# power_supplies.net
KiCad netlist of a schematic drawn in Altium Designer
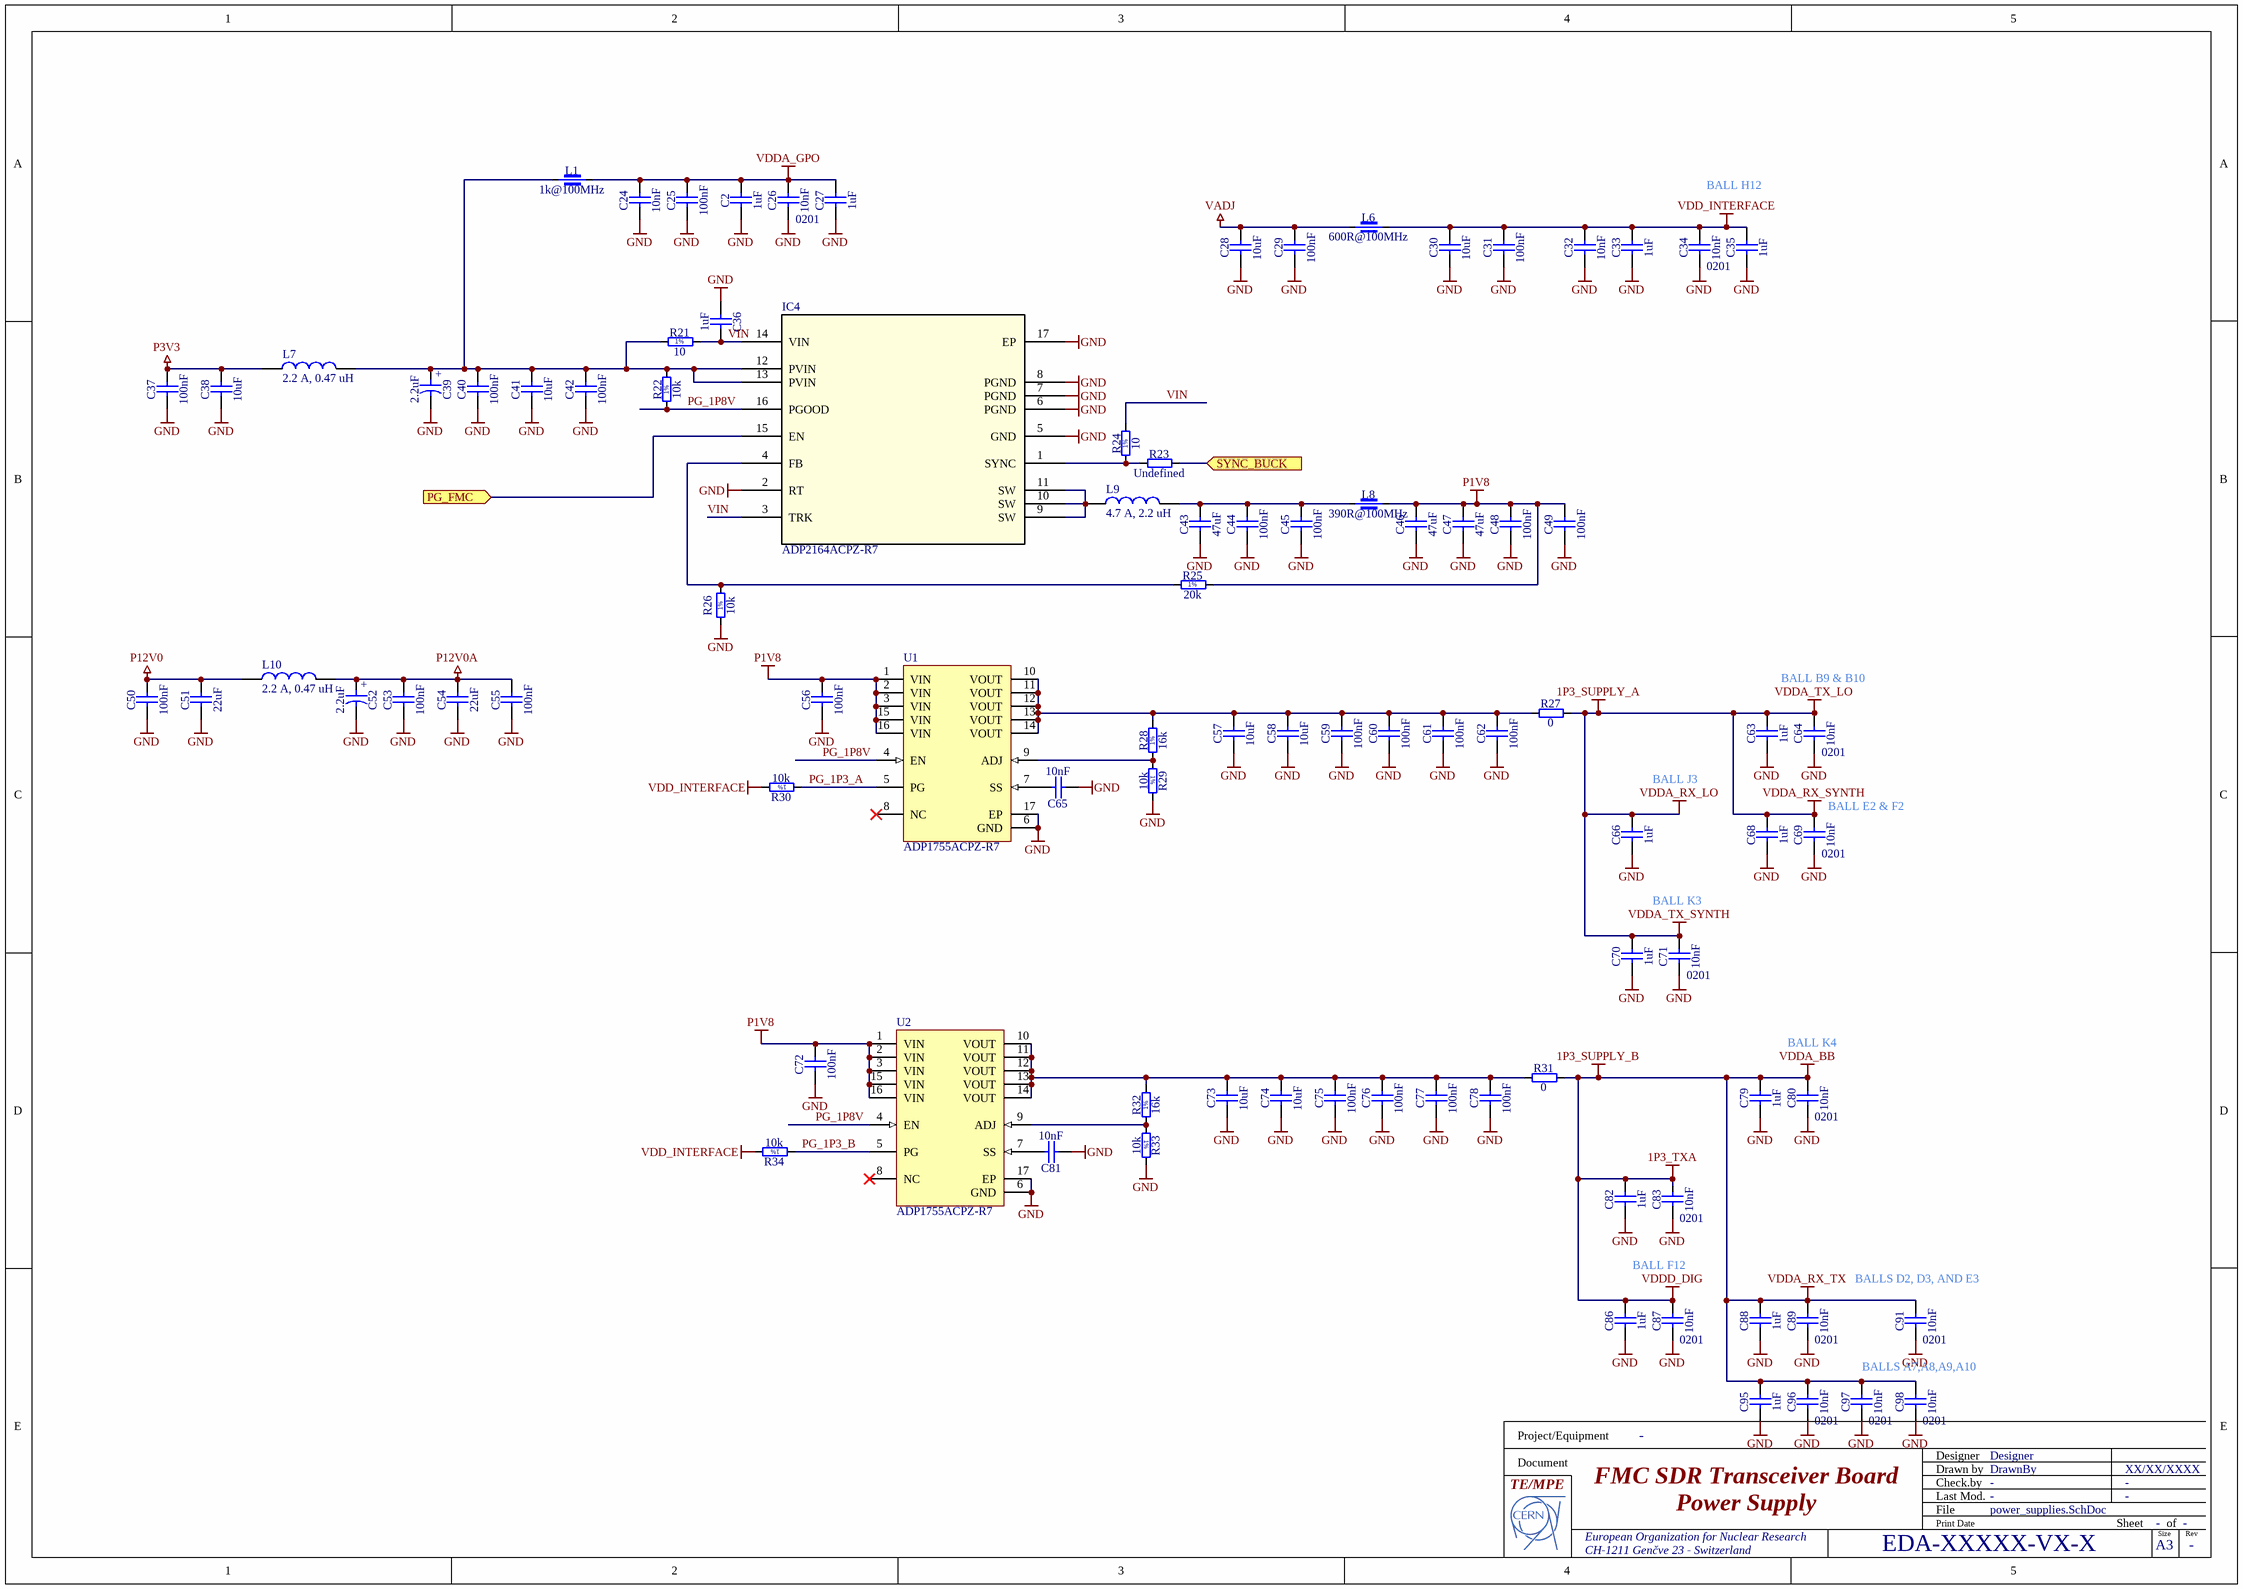
[diagram p0: power_supplies.SchDoc]

(export (version "E")
  (design (tool "Eeschema 10.0.6"))
  (components
    (comp (ref "C2")
      (value "1uF")
      (footprint "CAPC1005X55N")
      (description "Non-polarised capacitor")
      (fields
        (field (name "PART NUMBER") "CC0402_1UF_16V_10%_X5R")
        (field (name "VOLTAGE") "16V")
        (field (name "AUTHOR") "CERN DEM JLC")
      )
      (libsource (lib "Capacitors") (part "Capacitor - non polarized"))
    )
    (comp (ref "C24")
      (value "10nF")
      (footprint "CAPC1005X55N")
      (description "Non-polarised capacitor")
      (fields
        (field (name "PART NUMBER") "CC0402_10NF_16V_10%_X7R")
        (field (name "VOLTAGE") "16V")
        (field (name "AUTHOR") "CERN DEM JLC")
      )
      (libsource (lib "Capacitors") (part "Capacitor - non polarized"))
    )
    (comp (ref "C25")
      (value "100nF")
      (footprint "CAPC1005X55N")
      (description "Non-polarised capacitor")
      (fields
        (field (name "PART NUMBER") "CC0402_100NF_16V_10%_X7R")
        (field (name "VOLTAGE") "16V")
        (field (name "AUTHOR") "CERN DEM JLC")
      )
      (libsource (lib "Capacitors") (part "Capacitor - non polarized"))
    )
    (comp (ref "C26")
      (value "10nF")
      (footprint "CAPC0603X33N")
      (description "Non-polarised capacitor")
      (fields
        (field (name "PART NUMBER") "CC0201_10NF_10V_10%_X5R")
        (field (name "VOLTAGE") "10V")
        (field (name "CASE") "0201")
        (field (name "AUTHOR") "CERN DEM JLC")
      )
      (libsource (lib "Capacitors") (part "Capacitor - non polarized"))
    )
    (comp (ref "C27")
      (value "1uF")
      (footprint "CAPC1005X55N")
      (description "Non-polarised capacitor")
      (fields
        (field (name "PART NUMBER") "CC0402_1UF_16V_10%_X5R")
        (field (name "VOLTAGE") "16V")
        (field (name "AUTHOR") "CERN DEM JLC")
      )
      (libsource (lib "Capacitors") (part "Capacitor - non polarized"))
    )
    (comp (ref "C28")
      (value "10uF")
      (footprint "CAPC1608X87N")
      (description "Non-polarised capacitor")
      (fields
        (field (name "PART NUMBER") "CC0603_10UF_6.3V_20%_X5R")
        (field (name "VOLTAGE") "6.3V")
        (field (name "AUTHOR") "CERN DEM JLC")
      )
      (libsource (lib "Capacitors") (part "Capacitor - non polarized"))
    )
    (comp (ref "C29")
      (value "100nF")
      (footprint "CAPC1005X55N")
      (description "Non-polarised capacitor")
      (fields
        (field (name "PART NUMBER") "CC0402_100NF_16V_10%_X7R")
        (field (name "VOLTAGE") "16V")
        (field (name "AUTHOR") "CERN DEM JLC")
      )
      (libsource (lib "Capacitors") (part "Capacitor - non polarized"))
    )
    (comp (ref "C30")
      (value "10uF")
      (footprint "CAPC1608X87N")
      (description "Non-polarised capacitor")
      (fields
        (field (name "PART NUMBER") "CC0603_10UF_6.3V_20%_X5R")
        (field (name "VOLTAGE") "6.3V")
        (field (name "AUTHOR") "CERN DEM JLC")
      )
      (libsource (lib "Capacitors") (part "Capacitor - non polarized"))
    )
    (comp (ref "C31")
      (value "100nF")
      (footprint "CAPC1005X55N")
      (description "Non-polarised capacitor")
      (fields
        (field (name "PART NUMBER") "CC0402_100NF_16V_10%_X7R")
        (field (name "VOLTAGE") "16V")
        (field (name "AUTHOR") "CERN DEM JLC")
      )
      (libsource (lib "Capacitors") (part "Capacitor - non polarized"))
    )
    (comp (ref "C32")
      (value "10nF")
      (footprint "CAPC1005X55N")
      (description "Non-polarised capacitor")
      (fields
        (field (name "PART NUMBER") "CC0402_10NF_16V_10%_X7R")
        (field (name "VOLTAGE") "16V")
        (field (name "AUTHOR") "CERN DEM JLC")
      )
      (libsource (lib "Capacitors") (part "Capacitor - non polarized"))
    )
    (comp (ref "C33")
      (value "1uF")
      (footprint "CAPC1005X55N")
      (description "Non-polarised capacitor")
      (fields
        (field (name "PART NUMBER") "CC0402_1UF_16V_10%_X5R")
        (field (name "VOLTAGE") "16V")
        (field (name "AUTHOR") "CERN DEM JLC")
      )
      (libsource (lib "Capacitors") (part "Capacitor - non polarized"))
    )
    (comp (ref "C34")
      (value "10nF")
      (footprint "CAPC0603X33N")
      (description "Non-polarised capacitor")
      (fields
        (field (name "PART NUMBER") "CC0201_10NF_10V_10%_X5R")
        (field (name "VOLTAGE") "10V")
        (field (name "CASE") "0201")
        (field (name "AUTHOR") "CERN DEM JLC")
      )
      (libsource (lib "Capacitors") (part "Capacitor - non polarized"))
    )
    (comp (ref "C35")
      (value "1uF")
      (footprint "CAPC1005X55N")
      (description "Non-polarised capacitor")
      (fields
        (field (name "PART NUMBER") "CC0402_1UF_16V_10%_X5R")
        (field (name "VOLTAGE") "16V")
        (field (name "AUTHOR") "CERN DEM JLC")
      )
      (libsource (lib "Capacitors") (part "Capacitor - non polarized"))
    )
    (comp (ref "C36")
      (value "1uF")
      (footprint "CAPC1005X55N")
      (description "Non-polarised capacitor")
      (fields
        (field (name "PART NUMBER") "CC0402_1UF_16V_10%_X5R")
        (field (name "VOLTAGE") "16V")
        (field (name "AUTHOR") "CERN DEM JLC")
      )
      (libsource (lib "Capacitors") (part "Capacitor - non polarized"))
    )
    (comp (ref "C37")
      (value "100nF")
      (footprint "CAPC1005X55N")
      (description "Non-polarised capacitor")
      (fields
        (field (name "PART NUMBER") "CC0402_100NF_16V_10%_X7R")
        (field (name "VOLTAGE") "16V")
        (field (name "AUTHOR") "CERN DEM JLC")
      )
      (libsource (lib "Capacitors") (part "Capacitor - non polarized"))
    )
    (comp (ref "C38")
      (value "10uF")
      (footprint "CAPC1608X87N")
      (description "Non-polarised capacitor")
      (fields
        (field (name "PART NUMBER") "CC0603_10UF_6.3V_20%_X5R")
        (field (name "VOLTAGE") "6.3V")
        (field (name "AUTHOR") "CERN DEM JLC")
      )
      (libsource (lib "Capacitors") (part "Capacitor - non polarized"))
    )
    (comp (ref "C39")
      (value "2.2uF")
      (footprint "CAPMP3216X180N")
      (description "Polarised capacitor")
      (fields
        (field (name "PART NUMBER") "CTE3216-18_2.2UF_25V_10%")
        (field (name "VOLTAGE") "25V")
        (field (name "AUTHOR") "CERN DEM JLC")
      )
      (libsource (lib "Capacitors") (part "Capacitor - polarized"))
    )
    (comp (ref "C40")
      (value "100nF")
      (footprint "CAPC1005X55N")
      (description "Non-polarised capacitor")
      (fields
        (field (name "PART NUMBER") "CC0402_100NF_16V_10%_X7R")
        (field (name "VOLTAGE") "16V")
        (field (name "AUTHOR") "CERN DEM JLC")
      )
      (libsource (lib "Capacitors") (part "Capacitor - non polarized"))
    )
    (comp (ref "C41")
      (value "10uF")
      (footprint "CAPC1608X87N")
      (description "Non-polarised capacitor")
      (fields
        (field (name "PART NUMBER") "CC0603_10UF_6.3V_20%_X5R")
        (field (name "VOLTAGE") "6.3V")
        (field (name "AUTHOR") "CERN DEM JLC")
      )
      (libsource (lib "Capacitors") (part "Capacitor - non polarized"))
    )
    (comp (ref "C42")
      (value "100nF")
      (footprint "CAPC1005X55N")
      (description "Non-polarised capacitor")
      (fields
        (field (name "PART NUMBER") "CC0402_100NF_16V_10%_X7R")
        (field (name "VOLTAGE") "16V")
        (field (name "AUTHOR") "CERN DEM JLC")
      )
      (libsource (lib "Capacitors") (part "Capacitor - non polarized"))
    )
    (comp (ref "C43")
      (value "47uF")
      (footprint "CAPC3216X180N")
      (description "Non-polarised capacitor")
      (fields
        (field (name "PART NUMBER") "CC1206_47UF_25V_20%_X5R")
        (field (name "VOLTAGE") "25V")
        (field (name "AUTHOR") "CERN DEM JLC")
      )
      (libsource (lib "Capacitors") (part "Capacitor - non polarized"))
    )
    (comp (ref "C44")
      (value "100nF")
      (footprint "CAPC1005X55N")
      (description "Non-polarised capacitor")
      (fields
        (field (name "PART NUMBER") "CC0402_100NF_16V_10%_X7R")
        (field (name "VOLTAGE") "16V")
        (field (name "AUTHOR") "CERN DEM JLC")
      )
      (libsource (lib "Capacitors") (part "Capacitor - non polarized"))
    )
    (comp (ref "C45")
      (value "100nF")
      (footprint "CAPC1005X55N")
      (description "Non-polarised capacitor")
      (fields
        (field (name "PART NUMBER") "CC0402_100NF_16V_10%_X7R")
        (field (name "VOLTAGE") "16V")
        (field (name "AUTHOR") "CERN DEM JLC")
      )
      (libsource (lib "Capacitors") (part "Capacitor - non polarized"))
    )
    (comp (ref "C46")
      (value "47uF")
      (footprint "CAPC3216X180N")
      (description "Non-polarised capacitor")
      (fields
        (field (name "PART NUMBER") "CC1206_47UF_25V_20%_X5R")
        (field (name "VOLTAGE") "25V")
        (field (name "AUTHOR") "CERN DEM JLC")
      )
      (libsource (lib "Capacitors") (part "Capacitor - non polarized"))
    )
    (comp (ref "C47")
      (value "47uF")
      (footprint "CAPC3216X180N")
      (description "Non-polarised capacitor")
      (fields
        (field (name "PART NUMBER") "CC1206_47UF_25V_20%_X5R")
        (field (name "VOLTAGE") "25V")
        (field (name "AUTHOR") "CERN DEM JLC")
      )
      (libsource (lib "Capacitors") (part "Capacitor - non polarized"))
    )
    (comp (ref "C48")
      (value "100nF")
      (footprint "CAPC1005X55N")
      (description "Non-polarised capacitor")
      (fields
        (field (name "PART NUMBER") "CC0402_100NF_16V_10%_X7R")
        (field (name "VOLTAGE") "16V")
        (field (name "AUTHOR") "CERN DEM JLC")
      )
      (libsource (lib "Capacitors") (part "Capacitor - non polarized"))
    )
    (comp (ref "C49")
      (value "100nF")
      (footprint "CAPC1005X55N")
      (description "Non-polarised capacitor")
      (fields
        (field (name "PART NUMBER") "CC0402_100NF_16V_10%_X7R")
        (field (name "VOLTAGE") "16V")
        (field (name "AUTHOR") "CERN DEM JLC")
      )
      (libsource (lib "Capacitors") (part "Capacitor - non polarized"))
    )
    (comp (ref "C50")
      (value "100nF")
      (footprint "CAPC1005X55N")
      (description "Non-polarised capacitor")
      (fields
        (field (name "PART NUMBER") "CC0402_100NF_16V_10%_X7R")
        (field (name "VOLTAGE") "16V")
        (field (name "AUTHOR") "CERN DEM JLC")
      )
      (libsource (lib "Capacitors") (part "Capacitor - non polarized"))
    )
    (comp (ref "C51")
      (value "22uF")
      (footprint "CAPC3216X180N")
      (description "Non-polarised capacitor")
      (fields
        (field (name "PART NUMBER") "CC1206_22UF_35V_20%_JB_TDK_C3216JB1V226M160AC")
        (field (name "VOLTAGE") "35V")
        (field (name "AUTHOR") "CERN DEM JLC")
      )
      (libsource (lib "Capacitors") (part "Capacitor - non polarized"))
    )
    (comp (ref "C52")
      (value "2.2uF")
      (footprint "CAPMP3216X180N")
      (description "Polarised capacitor")
      (fields
        (field (name "PART NUMBER") "CTE3216-18_2.2UF_25V_10%")
        (field (name "VOLTAGE") "25V")
        (field (name "AUTHOR") "CERN DEM JLC")
      )
      (libsource (lib "Capacitors") (part "Capacitor - polarized"))
    )
    (comp (ref "C53")
      (value "100nF")
      (footprint "CAPC1005X55N")
      (description "Non-polarised capacitor")
      (fields
        (field (name "PART NUMBER") "CC0402_100NF_16V_10%_X7R")
        (field (name "VOLTAGE") "16V")
        (field (name "AUTHOR") "CERN DEM JLC")
      )
      (libsource (lib "Capacitors") (part "Capacitor - non polarized"))
    )
    (comp (ref "C54")
      (value "22uF")
      (footprint "CAPC3216X180N")
      (description "Non-polarised capacitor")
      (fields
        (field (name "PART NUMBER") "CC1206_22UF_35V_20%_JB_TDK_C3216JB1V226M160AC")
        (field (name "VOLTAGE") "35V")
        (field (name "AUTHOR") "CERN DEM JLC")
      )
      (libsource (lib "Capacitors") (part "Capacitor - non polarized"))
    )
    (comp (ref "C55")
      (value "100nF")
      (footprint "CAPC1005X55N")
      (description "Non-polarised capacitor")
      (fields
        (field (name "PART NUMBER") "CC0402_100NF_16V_10%_X7R")
        (field (name "VOLTAGE") "16V")
        (field (name "AUTHOR") "CERN DEM JLC")
      )
      (libsource (lib "Capacitors") (part "Capacitor - non polarized"))
    )
    (comp (ref "C56")
      (value "100nF")
      (footprint "CAPC1005X55N")
      (description "Non-polarised capacitor")
      (fields
        (field (name "PART NUMBER") "CC0402_100NF_16V_10%_X7R")
        (field (name "VOLTAGE") "16V")
        (field (name "AUTHOR") "CERN DEM JLC")
      )
      (libsource (lib "Capacitors") (part "Capacitor - non polarized"))
    )
    (comp (ref "C57")
      (value "10uF")
      (footprint "CAPC1608X87N")
      (description "Non-polarised capacitor")
      (fields
        (field (name "PART NUMBER") "CC0603_10UF_6.3V_20%_X5R")
        (field (name "VOLTAGE") "6.3V")
        (field (name "AUTHOR") "CERN DEM JLC")
      )
      (libsource (lib "Capacitors") (part "Capacitor - non polarized"))
    )
    (comp (ref "C58")
      (value "10uF")
      (footprint "CAPC1608X87N")
      (description "Non-polarised capacitor")
      (fields
        (field (name "PART NUMBER") "CC0603_10UF_6.3V_20%_X5R")
        (field (name "VOLTAGE") "6.3V")
        (field (name "AUTHOR") "CERN DEM JLC")
      )
      (libsource (lib "Capacitors") (part "Capacitor - non polarized"))
    )
    (comp (ref "C59")
      (value "100nF")
      (footprint "CAPC1005X55N")
      (description "Non-polarised capacitor")
      (fields
        (field (name "PART NUMBER") "CC0402_100NF_16V_10%_X7R")
        (field (name "VOLTAGE") "16V")
        (field (name "AUTHOR") "CERN DEM JLC")
      )
      (libsource (lib "Capacitors") (part "Capacitor - non polarized"))
    )
    (comp (ref "C60")
      (value "100nF")
      (footprint "CAPC1005X55N")
      (description "Non-polarised capacitor")
      (fields
        (field (name "PART NUMBER") "CC0402_100NF_16V_10%_X7R")
        (field (name "VOLTAGE") "16V")
        (field (name "AUTHOR") "CERN DEM JLC")
      )
      (libsource (lib "Capacitors") (part "Capacitor - non polarized"))
    )
    (comp (ref "C61")
      (value "100nF")
      (footprint "CAPC1005X55N")
      (description "Non-polarised capacitor")
      (fields
        (field (name "PART NUMBER") "CC0402_100NF_16V_10%_X7R")
        (field (name "VOLTAGE") "16V")
        (field (name "AUTHOR") "CERN DEM JLC")
      )
      (libsource (lib "Capacitors") (part "Capacitor - non polarized"))
    )
    (comp (ref "C62")
      (value "100nF")
      (footprint "CAPC1005X55N")
      (description "Non-polarised capacitor")
      (fields
        (field (name "PART NUMBER") "CC0402_100NF_16V_10%_X7R")
        (field (name "VOLTAGE") "16V")
        (field (name "AUTHOR") "CERN DEM JLC")
      )
      (libsource (lib "Capacitors") (part "Capacitor - non polarized"))
    )
    (comp (ref "C63")
      (value "1uF")
      (footprint "CAPC1005X55N")
      (description "Non-polarised capacitor")
      (fields
        (field (name "PART NUMBER") "CC0402_1UF_16V_10%_X5R")
        (field (name "VOLTAGE") "16V")
        (field (name "AUTHOR") "CERN DEM JLC")
      )
      (libsource (lib "Capacitors") (part "Capacitor - non polarized"))
    )
    (comp (ref "C64")
      (value "10nF")
      (footprint "CAPC0603X33N")
      (description "Non-polarised capacitor")
      (fields
        (field (name "PART NUMBER") "CC0201_10NF_10V_10%_X5R")
        (field (name "VOLTAGE") "10V")
        (field (name "CASE") "0201")
        (field (name "AUTHOR") "CERN DEM JLC")
      )
      (libsource (lib "Capacitors") (part "Capacitor - non polarized"))
    )
    (comp (ref "C65")
      (value "10nF")
      (footprint "CAPC1005X55N")
      (description "Non-polarised capacitor")
      (fields
        (field (name "PART NUMBER") "CC0402_10NF_16V_10%_X7R")
        (field (name "VOLTAGE") "16V")
        (field (name "AUTHOR") "CERN DEM JLC")
      )
      (libsource (lib "Capacitors") (part "Capacitor - non polarized"))
    )
    (comp (ref "C66")
      (value "1uF")
      (footprint "CAPC1005X55N")
      (description "Non-polarised capacitor")
      (fields
        (field (name "PART NUMBER") "CC0402_1UF_16V_10%_X5R")
        (field (name "VOLTAGE") "16V")
        (field (name "AUTHOR") "CERN DEM JLC")
      )
      (libsource (lib "Capacitors") (part "Capacitor - non polarized"))
    )
    (comp (ref "C68")
      (value "1uF")
      (footprint "CAPC1005X55N")
      (description "Non-polarised capacitor")
      (fields
        (field (name "PART NUMBER") "CC0402_1UF_16V_10%_X5R")
        (field (name "VOLTAGE") "16V")
        (field (name "AUTHOR") "CERN DEM JLC")
      )
      (libsource (lib "Capacitors") (part "Capacitor - non polarized"))
    )
    (comp (ref "C69")
      (value "10nF")
      (footprint "CAPC0603X33N")
      (description "Non-polarised capacitor")
      (fields
        (field (name "PART NUMBER") "CC0201_10NF_10V_10%_X5R")
        (field (name "VOLTAGE") "10V")
        (field (name "CASE") "0201")
        (field (name "AUTHOR") "CERN DEM JLC")
      )
      (libsource (lib "Capacitors") (part "Capacitor - non polarized"))
    )
    (comp (ref "C70")
      (value "1uF")
      (footprint "CAPC1005X55N")
      (description "Non-polarised capacitor")
      (fields
        (field (name "PART NUMBER") "CC0402_1UF_16V_10%_X5R")
        (field (name "VOLTAGE") "16V")
        (field (name "AUTHOR") "CERN DEM JLC")
      )
      (libsource (lib "Capacitors") (part "Capacitor - non polarized"))
    )
    (comp (ref "C71")
      (value "10nF")
      (footprint "CAPC0603X33N")
      (description "Non-polarised capacitor")
      (fields
        (field (name "PART NUMBER") "CC0201_10NF_10V_10%_X5R")
        (field (name "VOLTAGE") "10V")
        (field (name "CASE") "0201")
        (field (name "AUTHOR") "CERN DEM JLC")
      )
      (libsource (lib "Capacitors") (part "Capacitor - non polarized"))
    )
    (comp (ref "C72")
      (value "100nF")
      (footprint "CAPC1005X55N")
      (description "Non-polarised capacitor")
      (fields
        (field (name "PART NUMBER") "CC0402_100NF_16V_10%_X7R")
        (field (name "VOLTAGE") "16V")
        (field (name "AUTHOR") "CERN DEM JLC")
      )
      (libsource (lib "Capacitors") (part "Capacitor - non polarized"))
    )
    (comp (ref "C73")
      (value "10uF")
      (footprint "CAPC1608X87N")
      (description "Non-polarised capacitor")
      (fields
        (field (name "PART NUMBER") "CC0603_10UF_6.3V_20%_X5R")
        (field (name "VOLTAGE") "6.3V")
        (field (name "AUTHOR") "CERN DEM JLC")
      )
      (libsource (lib "Capacitors") (part "Capacitor - non polarized"))
    )
    (comp (ref "C74")
      (value "10uF")
      (footprint "CAPC1608X87N")
      (description "Non-polarised capacitor")
      (fields
        (field (name "PART NUMBER") "CC0603_10UF_6.3V_20%_X5R")
        (field (name "VOLTAGE") "6.3V")
        (field (name "AUTHOR") "CERN DEM JLC")
      )
      (libsource (lib "Capacitors") (part "Capacitor - non polarized"))
    )
    (comp (ref "C75")
      (value "100nF")
      (footprint "CAPC1005X55N")
      (description "Non-polarised capacitor")
      (fields
        (field (name "PART NUMBER") "CC0402_100NF_16V_10%_X7R")
        (field (name "VOLTAGE") "16V")
        (field (name "AUTHOR") "CERN DEM JLC")
      )
      (libsource (lib "Capacitors") (part "Capacitor - non polarized"))
    )
    (comp (ref "C76")
      (value "100nF")
      (footprint "CAPC1005X55N")
      (description "Non-polarised capacitor")
      (fields
        (field (name "PART NUMBER") "CC0402_100NF_16V_10%_X7R")
        (field (name "VOLTAGE") "16V")
        (field (name "AUTHOR") "CERN DEM JLC")
      )
      (libsource (lib "Capacitors") (part "Capacitor - non polarized"))
    )
    (comp (ref "C77")
      (value "100nF")
      (footprint "CAPC1005X55N")
      (description "Non-polarised capacitor")
      (fields
        (field (name "PART NUMBER") "CC0402_100NF_16V_10%_X7R")
        (field (name "VOLTAGE") "16V")
        (field (name "AUTHOR") "CERN DEM JLC")
      )
      (libsource (lib "Capacitors") (part "Capacitor - non polarized"))
    )
    (comp (ref "C78")
      (value "100nF")
      (footprint "CAPC1005X55N")
      (description "Non-polarised capacitor")
      (fields
        (field (name "PART NUMBER") "CC0402_100NF_16V_10%_X7R")
        (field (name "VOLTAGE") "16V")
        (field (name "AUTHOR") "CERN DEM JLC")
      )
      (libsource (lib "Capacitors") (part "Capacitor - non polarized"))
    )
    (comp (ref "C79")
      (value "1uF")
      (footprint "CAPC1005X55N")
      (description "Non-polarised capacitor")
      (fields
        (field (name "PART NUMBER") "CC0402_1UF_16V_10%_X5R")
        (field (name "VOLTAGE") "16V")
        (field (name "AUTHOR") "CERN DEM JLC")
      )
      (libsource (lib "Capacitors") (part "Capacitor - non polarized"))
    )
    (comp (ref "C80")
      (value "10nF")
      (footprint "CAPC0603X33N")
      (description "Non-polarised capacitor")
      (fields
        (field (name "PART NUMBER") "CC0201_10NF_10V_10%_X5R")
        (field (name "VOLTAGE") "10V")
        (field (name "CASE") "0201")
        (field (name "AUTHOR") "CERN DEM JLC")
      )
      (libsource (lib "Capacitors") (part "Capacitor - non polarized"))
    )
    (comp (ref "C81")
      (value "10nF")
      (footprint "CAPC1005X55N")
      (description "Non-polarised capacitor")
      (fields
        (field (name "PART NUMBER") "CC0402_10NF_16V_10%_X7R")
        (field (name "VOLTAGE") "16V")
        (field (name "AUTHOR") "CERN DEM JLC")
      )
      (libsource (lib "Capacitors") (part "Capacitor - non polarized"))
    )
    (comp (ref "C82")
      (value "1uF")
      (footprint "CAPC1005X55N")
      (description "Non-polarised capacitor")
      (fields
        (field (name "PART NUMBER") "CC0402_1UF_16V_10%_X5R")
        (field (name "VOLTAGE") "16V")
        (field (name "AUTHOR") "CERN DEM JLC")
      )
      (libsource (lib "Capacitors") (part "Capacitor - non polarized"))
    )
    (comp (ref "C83")
      (value "10nF")
      (footprint "CAPC0603X33N")
      (description "Non-polarised capacitor")
      (fields
        (field (name "PART NUMBER") "CC0201_10NF_10V_10%_X5R")
        (field (name "VOLTAGE") "10V")
        (field (name "CASE") "0201")
        (field (name "AUTHOR") "CERN DEM JLC")
      )
      (libsource (lib "Capacitors") (part "Capacitor - non polarized"))
    )
    (comp (ref "C86")
      (value "1uF")
      (footprint "CAPC1005X55N")
      (description "Non-polarised capacitor")
      (fields
        (field (name "PART NUMBER") "CC0402_1UF_16V_10%_X5R")
        (field (name "VOLTAGE") "16V")
        (field (name "AUTHOR") "CERN DEM JLC")
      )
      (libsource (lib "Capacitors") (part "Capacitor - non polarized"))
    )
    (comp (ref "C87")
      (value "10nF")
      (footprint "CAPC0603X33N")
      (description "Non-polarised capacitor")
      (fields
        (field (name "PART NUMBER") "CC0201_10NF_10V_10%_X5R")
        (field (name "VOLTAGE") "10V")
        (field (name "CASE") "0201")
        (field (name "AUTHOR") "CERN DEM JLC")
      )
      (libsource (lib "Capacitors") (part "Capacitor - non polarized"))
    )
    (comp (ref "C88")
      (value "1uF")
      (footprint "CAPC1005X55N")
      (description "Non-polarised capacitor")
      (fields
        (field (name "PART NUMBER") "CC0402_1UF_16V_10%_X5R")
        (field (name "VOLTAGE") "16V")
        (field (name "AUTHOR") "CERN DEM JLC")
      )
      (libsource (lib "Capacitors") (part "Capacitor - non polarized"))
    )
    (comp (ref "C89")
      (value "10nF")
      (footprint "CAPC0603X33N")
      (description "Non-polarised capacitor")
      (fields
        (field (name "PART NUMBER") "CC0201_10NF_10V_10%_X5R")
        (field (name "VOLTAGE") "10V")
        (field (name "CASE") "0201")
        (field (name "AUTHOR") "CERN DEM JLC")
      )
      (libsource (lib "Capacitors") (part "Capacitor - non polarized"))
    )
    (comp (ref "C91")
      (value "10nF")
      (footprint "CAPC0603X33N")
      (description "Non-polarised capacitor")
      (fields
        (field (name "PART NUMBER") "CC0201_10NF_10V_10%_X5R")
        (field (name "VOLTAGE") "10V")
        (field (name "CASE") "0201")
        (field (name "AUTHOR") "CERN DEM JLC")
      )
      (libsource (lib "Capacitors") (part "Capacitor - non polarized"))
    )
    (comp (ref "C95")
      (value "1uF")
      (footprint "CAPC1005X55N")
      (description "Non-polarised capacitor")
      (fields
        (field (name "PART NUMBER") "CC0402_1UF_16V_10%_X5R")
        (field (name "VOLTAGE") "16V")
        (field (name "AUTHOR") "CERN DEM JLC")
      )
      (libsource (lib "Capacitors") (part "Capacitor - non polarized"))
    )
    (comp (ref "C96")
      (value "10nF")
      (footprint "CAPC0603X33N")
      (description "Non-polarised capacitor")
      (fields
        (field (name "PART NUMBER") "CC0201_10NF_10V_10%_X5R")
        (field (name "VOLTAGE") "10V")
        (field (name "CASE") "0201")
        (field (name "AUTHOR") "CERN DEM JLC")
      )
      (libsource (lib "Capacitors") (part "Capacitor - non polarized"))
    )
    (comp (ref "C97")
      (value "10nF")
      (footprint "CAPC0603X33N")
      (description "Non-polarised capacitor")
      (fields
        (field (name "PART NUMBER") "CC0201_10NF_10V_10%_X5R")
        (field (name "VOLTAGE") "10V")
        (field (name "CASE") "0201")
        (field (name "AUTHOR") "CERN DEM JLC")
      )
      (libsource (lib "Capacitors") (part "Capacitor - non polarized"))
    )
    (comp (ref "C98")
      (value "10nF")
      (footprint "CAPC0603X33N")
      (description "Non-polarised capacitor")
      (fields
        (field (name "PART NUMBER") "CC0201_10NF_10V_10%_X5R")
        (field (name "VOLTAGE") "10V")
        (field (name "CASE") "0201")
        (field (name "AUTHOR") "CERN DEM JLC")
      )
      (libsource (lib "Capacitors") (part "Capacitor - non polarized"))
    )
    (comp (ref "IC4")
      (value "ADP2164ACPZ-R7")
      (footprint "CP_16_26")
      (description "6.5 V, 4 A, High Efficiency,Step-Down,DC-to-DC Regulator")
      (fields (field (name "COPYRIGHT") "Copyright (C) 2018 Accelerated Designs. All rights reserved"))
      (libsource (lib "LIBRARY_SCH") (part "PM_ADP2164ACPZ-R7"))
    )
    (comp (ref "L1")
      (value "1k@100MHz")
      (footprint "INDC1005X55N")
      (fields
        (field (name "PART NUMBER") "IND0402_MURATA_BLM15HD102SN1")
        (field (name "POWER") "250mA")
        (field (name "TOLERANCE") "±25%")
        (field (name "AUTHOR") "CERN DEM JLC")
      )
      (libsource (lib "Inductors & Transformers") (part "Ferrite Bead"))
    )
    (comp (ref "L6")
      (value "600R@100MHz")
      (footprint "INDC1608X75N")
      (fields
        (field (name "PART NUMBER") "IND0603_TDK_MMZ1608B601CTAH0")
        (field (name "POWER") "500mA")
        (field (name "TOLERANCE") "±25%")
        (field (name "AUTHOR") "CERN DEM JMW")
      )
      (libsource (lib "Inductors & Transformers") (part "Ferrite Bead"))
    )
    (comp (ref "L7")
      (value "2.2 A, 0.47 uH")
      (footprint "WE-MAIA_2506")
      (description "WE-MAIA SMD Power Inductor, size 2506, 2.2 A, 0.47 uH")
      (fields (field (name "PART NUMBER") "784383210047") (field (name "PUBLISHER") "Wurth Elektronik"))
      (libsource (lib "ALTIUM-WE-MAIA-rev17b") (part "784383210047"))
    )
    (comp (ref "L8")
      (value "390R@100MHz")
      (footprint "INDC1608X95N")
      (fields
        (field (name "PART NUMBER") "IND0603_TDK_MPZ1608R391A")
        (field (name "POWER") "1.2A")
        (field (name "TOLERANCE") "±25%")
        (field (name "AUTHOR") "CERN DEM JLC")
      )
      (libsource (lib "Inductors & Transformers") (part "Ferrite Bead"))
    )
    (comp (ref "L9")
      (value "4.7 A, 2.2 uH")
      (footprint "WE-MAIA_4020")
      (description "WE-MAIA SMD Power Inductor, size 4020, 4.7 A, 2.2 uH")
      (fields (field (name "PART NUMBER") "78438356022") (field (name "PUBLISHER") "Wurth Elektronik"))
      (libsource (lib "ALTIUM-WE-MAIA-rev17b") (part "78438356022"))
    )
    (comp (ref "L10")
      (value "2.2 A, 0.47 uH")
      (footprint "WE-MAIA_2506")
      (description "WE-MAIA SMD Power Inductor, size 2506, 2.2 A, 0.47 uH")
      (fields (field (name "PART NUMBER") "784383210047") (field (name "PUBLISHER") "Wurth Elektronik"))
      (libsource (lib "ALTIUM-WE-MAIA-rev17b") (part "784383210047"))
    )
    (comp (ref "R21")
      (value "10")
      (footprint "RESC1608X55N")
      (description "Resistor - 1%")
      (fields
        (field (name "PART NUMBER") "R0603_10R_1%_0.1W_200PPM")
        (field (name "POWER") "0.1W")
        (field (name "AUTHOR") "CERN DEM JLC")
      )
      (libsource (lib "Resistors") (part "Resistor - 1%"))
    )
    (comp (ref "R22")
      (value "10k")
      (footprint "RESC1005X40N")
      (description "Resistor - 1%")
      (fields
        (field (name "PART NUMBER") "R0402_10K_1%_0.0625W_100PPM")
        (field (name "POWER") "0.0625W")
        (field (name "AUTHOR") "CERN DEM JLC")
      )
      (libsource (lib "Resistors") (part "Resistor - 1%"))
    )
    (comp (ref "R23")
      (value "Undefined")
      (footprint "RESC1608X55N")
      (description "Resistor")
      (fields (field (name "PART NUMBER") "R0603_NO-VALUE") (field (name "AUTHOR") "CERN DEM JLC"))
      (libsource (lib "Resistors") (part "Resistor"))
    )
    (comp (ref "R24")
      (value "10")
      (footprint "RESC1608X55N")
      (description "Resistor - 1%")
      (fields
        (field (name "PART NUMBER") "R0603_10R_1%_0.1W_200PPM")
        (field (name "POWER") "0.1W")
        (field (name "AUTHOR") "CERN DEM JLC")
      )
      (libsource (lib "Resistors") (part "Resistor - 1%"))
    )
    (comp (ref "R25")
      (value "20k")
      (footprint "RESC1005X40N")
      (description "Resistor - 1%")
      (fields
        (field (name "PART NUMBER") "R0402_20K_1%_0.0625W_100PPM")
        (field (name "POWER") "0.0625W")
        (field (name "AUTHOR") "CERN DEM JLC")
      )
      (libsource (lib "Resistors") (part "Resistor - 1%"))
    )
    (comp (ref "R26")
      (value "10k")
      (footprint "RESC1005X40N")
      (description "Resistor - 1%")
      (fields
        (field (name "PART NUMBER") "R0402_10K_1%_0.0625W_100PPM")
        (field (name "POWER") "0.0625W")
        (field (name "AUTHOR") "CERN DEM JLC")
      )
      (libsource (lib "Resistors") (part "Resistor - 1%"))
    )
    (comp (ref "R27")
      (value "0")
      (footprint "RESC1608X55N")
      (description "Resistor")
      (fields
        (field (name "PART NUMBER") "R0603_0R_JUMPER")
        (field (name "MANUFACTURER") "GENERIC")
        (field (name "AUTHOR") "CERN DEM JLC")
      )
      (libsource (lib "Resistors") (part "Resistor"))
    )
    (comp (ref "R28")
      (value "16k")
      (footprint "RESC1005X40N")
      (description "Resistor - 1%")
      (fields
        (field (name "PART NUMBER") "R0402_16K_1%_0.0625W_100PPM")
        (field (name "POWER") "0.0625W")
        (field (name "AUTHOR") "CERN DEM JLC")
      )
      (libsource (lib "Resistors") (part "Resistor - 1%"))
    )
    (comp (ref "R29")
      (value "10k")
      (footprint "RESC1005X40N")
      (description "Resistor - 1%")
      (fields
        (field (name "PART NUMBER") "R0402_10K_1%_0.0625W_100PPM")
        (field (name "POWER") "0.0625W")
        (field (name "AUTHOR") "CERN DEM JLC")
      )
      (libsource (lib "Resistors") (part "Resistor - 1%"))
    )
    (comp (ref "R30")
      (value "10k")
      (footprint "RESC1005X40N")
      (description "Resistor - 1%")
      (fields
        (field (name "PART NUMBER") "R0402_10K_1%_0.0625W_100PPM")
        (field (name "POWER") "0.0625W")
        (field (name "AUTHOR") "CERN DEM JLC")
      )
      (libsource (lib "Resistors") (part "Resistor - 1%"))
    )
    (comp (ref "R31")
      (value "0")
      (footprint "RESC1608X55N")
      (description "Resistor")
      (fields
        (field (name "PART NUMBER") "R0603_0R_JUMPER")
        (field (name "MANUFACTURER") "GENERIC")
        (field (name "AUTHOR") "CERN DEM JLC")
      )
      (libsource (lib "Resistors") (part "Resistor"))
    )
    (comp (ref "R32")
      (value "16k")
      (footprint "RESC1005X40N")
      (description "Resistor - 1%")
      (fields
        (field (name "PART NUMBER") "R0402_16K_1%_0.0625W_100PPM")
        (field (name "POWER") "0.0625W")
        (field (name "AUTHOR") "CERN DEM JLC")
      )
      (libsource (lib "Resistors") (part "Resistor - 1%"))
    )
    (comp (ref "R33")
      (value "10k")
      (footprint "RESC1005X40N")
      (description "Resistor - 1%")
      (fields
        (field (name "PART NUMBER") "R0402_10K_1%_0.0625W_100PPM")
        (field (name "POWER") "0.0625W")
        (field (name "AUTHOR") "CERN DEM JLC")
      )
      (libsource (lib "Resistors") (part "Resistor - 1%"))
    )
    (comp (ref "R34")
      (value "10k")
      (footprint "RESC1005X40N")
      (description "Resistor - 1%")
      (fields
        (field (name "PART NUMBER") "R0402_10K_1%_0.0625W_100PPM")
        (field (name "POWER") "0.0625W")
        (field (name "AUTHOR") "CERN DEM JLC")
      )
      (libsource (lib "Resistors") (part "Resistor - 1%"))
    )
    (comp (ref "U1")
      (value "ADP1755ACPZ-R7")
      (footprint "CP-16-4_L")
      (fields (field (name "MANUFACTURER") "Analog Devices"))
      (libsource (lib "Altium Content Vault") (part "ADI-ADP1755-CP-16-4"))
    )
    (comp (ref "U2")
      (value "ADP1755ACPZ-R7")
      (footprint "CP-16-4_L")
      (fields (field (name "MANUFACTURER") "Analog Devices"))
      (libsource (lib "Altium Content Vault") (part "ADI-ADP1755-CP-16-4"))
    )
  )
  (nets
    (net (code "1") (name "/PG_1P3_A") (class "Default")
      (node (ref "R30") (pin "1") (pinfunction "1_1") (pintype "passive"))
      (node (ref "U1") (pin "5") (pinfunction "PG_5") (pintype "open_collector"))
    )
    (net (code "2") (name "/PG_1P3_B") (class "Default")
      (node (ref "R34") (pin "1") (pinfunction "1_1") (pintype "passive"))
      (node (ref "U2") (pin "5") (pinfunction "PG_5") (pintype "open_collector"))
    )
    (net (code "3") (name "/PG_1P8V") (class "Default")
      (node (ref "IC4") (pin "16") (pinfunction "PGOOD_16") (pintype "passive"))
      (node (ref "R22") (pin "1") (pinfunction "1_1") (pintype "passive"))
      (node (ref "U1") (pin "4") (pinfunction "EN_4") (pintype "input"))
      (node (ref "U2") (pin "4") (pinfunction "EN_4") (pintype "input"))
    )
    (net (code "4") (name "/PG_FMC") (class "Default")
      (node (ref "IC4") (pin "15") (pinfunction "EN_15") (pintype "passive"))
    )
    (net (code "5") (name "/SYNC_BUCK") (class "Default")
      (node (ref "R23") (pin "2") (pinfunction "2_2") (pintype "passive"))
    )
    (net (code "6") (name "/VIN") (class "Default")
      (node (ref "C36") (pin "2") (pinfunction "2_2") (pintype "passive"))
      (node (ref "IC4") (pin "14") (pinfunction "VIN_14") (pintype "passive"))
      (node (ref "IC4") (pin "3") (pinfunction "TRK_3") (pintype "passive"))
      (node (ref "R21") (pin "2") (pinfunction "2_2") (pintype "passive"))
      (node (ref "R24") (pin "2") (pinfunction "2_2") (pintype "passive"))
    )
    (net (code "7") (name "1P3_SUPPLY_A") (class "Default")
      (node (ref "C63") (pin "2") (pinfunction "2_2") (pintype "passive"))
      (node (ref "C64") (pin "2") (pinfunction "2_2") (pintype "passive"))
      (node (ref "C66") (pin "2") (pinfunction "2_2") (pintype "passive"))
      (node (ref "C68") (pin "2") (pinfunction "2_2") (pintype "passive"))
      (node (ref "C69") (pin "2") (pinfunction "2_2") (pintype "passive"))
      (node (ref "C70") (pin "2") (pinfunction "2_2") (pintype "passive"))
      (node (ref "C71") (pin "2") (pinfunction "2_2") (pintype "passive"))
      (node (ref "R27") (pin "2") (pinfunction "2_2") (pintype "passive"))
    )
    (net (code "8") (name "1P3_SUPPLY_B") (class "Default")
      (node (ref "C79") (pin "2") (pinfunction "2_2") (pintype "passive"))
      (node (ref "C80") (pin "2") (pinfunction "2_2") (pintype "passive"))
      (node (ref "C82") (pin "2") (pinfunction "2_2") (pintype "passive"))
      (node (ref "C83") (pin "2") (pinfunction "2_2") (pintype "passive"))
      (node (ref "C86") (pin "2") (pinfunction "2_2") (pintype "passive"))
      (node (ref "C87") (pin "2") (pinfunction "2_2") (pintype "passive"))
      (node (ref "C88") (pin "2") (pinfunction "2_2") (pintype "passive"))
      (node (ref "C89") (pin "2") (pinfunction "2_2") (pintype "passive"))
      (node (ref "C91") (pin "2") (pinfunction "2_2") (pintype "passive"))
      (node (ref "C95") (pin "2") (pinfunction "2_2") (pintype "passive"))
      (node (ref "C96") (pin "2") (pinfunction "2_2") (pintype "passive"))
      (node (ref "C97") (pin "2") (pinfunction "2_2") (pintype "passive"))
      (node (ref "C98") (pin "2") (pinfunction "2_2") (pintype "passive"))
      (node (ref "R31") (pin "2") (pinfunction "2_2") (pintype "passive"))
    )
    (net (code "9") (name "GND") (class "Default")
      (node (ref "C2") (pin "1") (pinfunction "1_1") (pintype "passive"))
      (node (ref "C24") (pin "1") (pinfunction "1_1") (pintype "passive"))
      (node (ref "C25") (pin "1") (pinfunction "1_1") (pintype "passive"))
      (node (ref "C26") (pin "1") (pinfunction "1_1") (pintype "passive"))
      (node (ref "C27") (pin "1") (pinfunction "1_1") (pintype "passive"))
      (node (ref "C28") (pin "1") (pinfunction "1_1") (pintype "passive"))
      (node (ref "C29") (pin "1") (pinfunction "1_1") (pintype "passive"))
      (node (ref "C30") (pin "1") (pinfunction "1_1") (pintype "passive"))
      (node (ref "C31") (pin "1") (pinfunction "1_1") (pintype "passive"))
      (node (ref "C32") (pin "1") (pinfunction "1_1") (pintype "passive"))
      (node (ref "C33") (pin "1") (pinfunction "1_1") (pintype "passive"))
      (node (ref "C34") (pin "1") (pinfunction "1_1") (pintype "passive"))
      (node (ref "C35") (pin "1") (pinfunction "1_1") (pintype "passive"))
      (node (ref "C36") (pin "1") (pinfunction "1_1") (pintype "passive"))
      (node (ref "C37") (pin "1") (pinfunction "1_1") (pintype "passive"))
      (node (ref "C38") (pin "1") (pinfunction "1_1") (pintype "passive"))
      (node (ref "C39") (pin "2") (pinfunction "2_2") (pintype "passive"))
      (node (ref "C40") (pin "1") (pinfunction "1_1") (pintype "passive"))
      (node (ref "C41") (pin "1") (pinfunction "1_1") (pintype "passive"))
      (node (ref "C42") (pin "1") (pinfunction "1_1") (pintype "passive"))
      (node (ref "C43") (pin "1") (pinfunction "1_1") (pintype "passive"))
      (node (ref "C44") (pin "1") (pinfunction "1_1") (pintype "passive"))
      (node (ref "C45") (pin "1") (pinfunction "1_1") (pintype "passive"))
      (node (ref "C46") (pin "1") (pinfunction "1_1") (pintype "passive"))
      (node (ref "C47") (pin "1") (pinfunction "1_1") (pintype "passive"))
      (node (ref "C48") (pin "1") (pinfunction "1_1") (pintype "passive"))
      (node (ref "C49") (pin "1") (pinfunction "1_1") (pintype "passive"))
      (node (ref "C50") (pin "1") (pinfunction "1_1") (pintype "passive"))
      (node (ref "C51") (pin "1") (pinfunction "1_1") (pintype "passive"))
      (node (ref "C52") (pin "2") (pinfunction "2_2") (pintype "passive"))
      (node (ref "C53") (pin "1") (pinfunction "1_1") (pintype "passive"))
      (node (ref "C54") (pin "1") (pinfunction "1_1") (pintype "passive"))
      (node (ref "C55") (pin "1") (pinfunction "1_1") (pintype "passive"))
      (node (ref "C56") (pin "1") (pinfunction "1_1") (pintype "passive"))
      (node (ref "C57") (pin "1") (pinfunction "1_1") (pintype "passive"))
      (node (ref "C58") (pin "1") (pinfunction "1_1") (pintype "passive"))
      (node (ref "C59") (pin "1") (pinfunction "1_1") (pintype "passive"))
      (node (ref "C60") (pin "1") (pinfunction "1_1") (pintype "passive"))
      (node (ref "C61") (pin "1") (pinfunction "1_1") (pintype "passive"))
      (node (ref "C62") (pin "1") (pinfunction "1_1") (pintype "passive"))
      (node (ref "C63") (pin "1") (pinfunction "1_1") (pintype "passive"))
      (node (ref "C64") (pin "1") (pinfunction "1_1") (pintype "passive"))
      (node (ref "C65") (pin "1") (pinfunction "1_1") (pintype "passive"))
      (node (ref "C66") (pin "1") (pinfunction "1_1") (pintype "passive"))
      (node (ref "C68") (pin "1") (pinfunction "1_1") (pintype "passive"))
      (node (ref "C69") (pin "1") (pinfunction "1_1") (pintype "passive"))
      (node (ref "C70") (pin "1") (pinfunction "1_1") (pintype "passive"))
      (node (ref "C71") (pin "1") (pinfunction "1_1") (pintype "passive"))
      (node (ref "C72") (pin "1") (pinfunction "1_1") (pintype "passive"))
      (node (ref "C73") (pin "1") (pinfunction "1_1") (pintype "passive"))
      (node (ref "C74") (pin "1") (pinfunction "1_1") (pintype "passive"))
      (node (ref "C75") (pin "1") (pinfunction "1_1") (pintype "passive"))
      (node (ref "C76") (pin "1") (pinfunction "1_1") (pintype "passive"))
      (node (ref "C77") (pin "1") (pinfunction "1_1") (pintype "passive"))
      (node (ref "C78") (pin "1") (pinfunction "1_1") (pintype "passive"))
      (node (ref "C79") (pin "1") (pinfunction "1_1") (pintype "passive"))
      (node (ref "C80") (pin "1") (pinfunction "1_1") (pintype "passive"))
      (node (ref "C81") (pin "1") (pinfunction "1_1") (pintype "passive"))
      (node (ref "C82") (pin "1") (pinfunction "1_1") (pintype "passive"))
      (node (ref "C83") (pin "1") (pinfunction "1_1") (pintype "passive"))
      (node (ref "C86") (pin "1") (pinfunction "1_1") (pintype "passive"))
      (node (ref "C87") (pin "1") (pinfunction "1_1") (pintype "passive"))
      (node (ref "C88") (pin "1") (pinfunction "1_1") (pintype "passive"))
      (node (ref "C89") (pin "1") (pinfunction "1_1") (pintype "passive"))
      (node (ref "C91") (pin "1") (pinfunction "1_1") (pintype "passive"))
      (node (ref "C95") (pin "1") (pinfunction "1_1") (pintype "passive"))
      (node (ref "C96") (pin "1") (pinfunction "1_1") (pintype "passive"))
      (node (ref "C97") (pin "1") (pinfunction "1_1") (pintype "passive"))
      (node (ref "C98") (pin "1") (pinfunction "1_1") (pintype "passive"))
      (node (ref "IC4") (pin "17") (pinfunction "EP_17") (pintype "passive"))
      (node (ref "IC4") (pin "2") (pinfunction "RT_2") (pintype "passive"))
      (node (ref "IC4") (pin "5") (pinfunction "GND_5") (pintype "passive"))
      (node (ref "IC4") (pin "6") (pinfunction "PGND_6") (pintype "passive"))
      (node (ref "IC4") (pin "7") (pinfunction "PGND_7") (pintype "passive"))
      (node (ref "IC4") (pin "8") (pinfunction "PGND_8") (pintype "passive"))
      (node (ref "R26") (pin "1") (pinfunction "1_1") (pintype "passive"))
      (node (ref "R29") (pin "2") (pinfunction "2_2") (pintype "passive"))
      (node (ref "R33") (pin "2") (pinfunction "2_2") (pintype "passive"))
      (node (ref "U1") (pin "17") (pinfunction "EP_17") (pintype "power_in"))
      (node (ref "U1") (pin "6") (pinfunction "GND_6") (pintype "power_in"))
      (node (ref "U2") (pin "17") (pinfunction "EP_17") (pintype "power_in"))
      (node (ref "U2") (pin "6") (pinfunction "GND_6") (pintype "power_in"))
    )
    (net (code "10") (name "Net-(C39-Pad1)") (class "Default")
      (node (ref "C39") (pin "1") (pinfunction "1_1") (pintype "passive"))
      (node (ref "C40") (pin "2") (pinfunction "2_2") (pintype "passive"))
      (node (ref "C41") (pin "2") (pinfunction "2_2") (pintype "passive"))
      (node (ref "C42") (pin "2") (pinfunction "2_2") (pintype "passive"))
      (node (ref "IC4") (pin "12") (pinfunction "PVIN_12") (pintype "passive"))
      (node (ref "IC4") (pin "13") (pinfunction "PVIN_13") (pintype "passive"))
      (node (ref "L1") (pin "1") (pinfunction "1_1") (pintype "passive"))
      (node (ref "L7") (pin "2") (pinfunction "2_2") (pintype "passive"))
      (node (ref "R21") (pin "1") (pinfunction "1_1") (pintype "passive"))
      (node (ref "R22") (pin "2") (pinfunction "2_2") (pintype "passive"))
    )
    (net (code "11") (name "Net-(C43-Pad2)") (class "Default")
      (node (ref "C43") (pin "2") (pinfunction "2_2") (pintype "passive"))
      (node (ref "C44") (pin "2") (pinfunction "2_2") (pintype "passive"))
      (node (ref "C45") (pin "2") (pinfunction "2_2") (pintype "passive"))
      (node (ref "L8") (pin "1") (pinfunction "1_1") (pintype "passive"))
      (node (ref "L9") (pin "2") (pinfunction "2_2") (pintype "passive"))
    )
    (net (code "12") (name "Net-(C57-Pad2)") (class "Default")
      (node (ref "C57") (pin "2") (pinfunction "2_2") (pintype "passive"))
      (node (ref "C58") (pin "2") (pinfunction "2_2") (pintype "passive"))
      (node (ref "C59") (pin "2") (pinfunction "2_2") (pintype "passive"))
      (node (ref "C60") (pin "2") (pinfunction "2_2") (pintype "passive"))
      (node (ref "C61") (pin "2") (pinfunction "2_2") (pintype "passive"))
      (node (ref "C62") (pin "2") (pinfunction "2_2") (pintype "passive"))
      (node (ref "R27") (pin "1") (pinfunction "1_1") (pintype "passive"))
      (node (ref "R28") (pin "2") (pinfunction "2_2") (pintype "passive"))
      (node (ref "U1") (pin "10") (pinfunction "VOUT_10") (pintype "power_in"))
      (node (ref "U1") (pin "11") (pinfunction "VOUT_11") (pintype "power_in"))
      (node (ref "U1") (pin "12") (pinfunction "VOUT_12") (pintype "power_in"))
      (node (ref "U1") (pin "13") (pinfunction "VOUT_13") (pintype "power_in"))
      (node (ref "U1") (pin "14") (pinfunction "VOUT_14") (pintype "power_in"))
    )
    (net (code "13") (name "Net-(C73-Pad2)") (class "Default")
      (node (ref "C73") (pin "2") (pinfunction "2_2") (pintype "passive"))
      (node (ref "C74") (pin "2") (pinfunction "2_2") (pintype "passive"))
      (node (ref "C75") (pin "2") (pinfunction "2_2") (pintype "passive"))
      (node (ref "C76") (pin "2") (pinfunction "2_2") (pintype "passive"))
      (node (ref "C77") (pin "2") (pinfunction "2_2") (pintype "passive"))
      (node (ref "C78") (pin "2") (pinfunction "2_2") (pintype "passive"))
      (node (ref "R31") (pin "1") (pinfunction "1_1") (pintype "passive"))
      (node (ref "R32") (pin "2") (pinfunction "2_2") (pintype "passive"))
      (node (ref "U2") (pin "10") (pinfunction "VOUT_10") (pintype "power_in"))
      (node (ref "U2") (pin "11") (pinfunction "VOUT_11") (pintype "power_in"))
      (node (ref "U2") (pin "12") (pinfunction "VOUT_12") (pintype "power_in"))
      (node (ref "U2") (pin "13") (pinfunction "VOUT_13") (pintype "power_in"))
      (node (ref "U2") (pin "14") (pinfunction "VOUT_14") (pintype "power_in"))
    )
    (net (code "14") (name "Net-(IC4-FB)") (class "Default")
      (node (ref "IC4") (pin "4") (pinfunction "FB_4") (pintype "passive"))
      (node (ref "R25") (pin "1") (pinfunction "1_1") (pintype "passive"))
      (node (ref "R26") (pin "2") (pinfunction "2_2") (pintype "passive"))
    )
    (net (code "15") (name "Net-(IC4-SW-Pad10)") (class "Default")
      (node (ref "IC4") (pin "10") (pinfunction "SW_10") (pintype "passive"))
      (node (ref "IC4") (pin "11") (pinfunction "SW_11") (pintype "passive"))
      (node (ref "IC4") (pin "9") (pinfunction "SW_9") (pintype "passive"))
      (node (ref "L9") (pin "1") (pinfunction "1_1") (pintype "passive"))
    )
    (net (code "16") (name "Net-(IC4-SYNC)") (class "Default")
      (node (ref "IC4") (pin "1") (pinfunction "SYNC_1") (pintype "passive"))
      (node (ref "R23") (pin "1") (pinfunction "1_1") (pintype "passive"))
      (node (ref "R24") (pin "1") (pinfunction "1_1") (pintype "passive"))
    )
    (net (code "17") (name "Net-(U1-ADJ)") (class "Default")
      (node (ref "R28") (pin "1") (pinfunction "1_1") (pintype "passive"))
      (node (ref "R29") (pin "1") (pinfunction "1_1") (pintype "passive"))
      (node (ref "U1") (pin "9") (pinfunction "ADJ_9") (pintype "input"))
    )
    (net (code "18") (name "Net-(U1-SS)") (class "Default")
      (node (ref "C65") (pin "2") (pinfunction "2_2") (pintype "passive"))
      (node (ref "U1") (pin "7") (pinfunction "SS_7") (pintype "input"))
    )
    (net (code "19") (name "Net-(U2-ADJ)") (class "Default")
      (node (ref "R32") (pin "1") (pinfunction "1_1") (pintype "passive"))
      (node (ref "R33") (pin "1") (pinfunction "1_1") (pintype "passive"))
      (node (ref "U2") (pin "9") (pinfunction "ADJ_9") (pintype "input"))
    )
    (net (code "20") (name "Net-(U2-SS)") (class "Default")
      (node (ref "C81") (pin "2") (pinfunction "2_2") (pintype "passive"))
      (node (ref "U2") (pin "7") (pinfunction "SS_7") (pintype "input"))
    )
    (net (code "21") (name "P1V8") (class "Default")
      (node (ref "C46") (pin "2") (pinfunction "2_2") (pintype "passive"))
      (node (ref "C47") (pin "2") (pinfunction "2_2") (pintype "passive"))
      (node (ref "C48") (pin "2") (pinfunction "2_2") (pintype "passive"))
      (node (ref "C49") (pin "2") (pinfunction "2_2") (pintype "passive"))
      (node (ref "C56") (pin "2") (pinfunction "2_2") (pintype "passive"))
      (node (ref "C72") (pin "2") (pinfunction "2_2") (pintype "passive"))
      (node (ref "L8") (pin "2") (pinfunction "2_2") (pintype "passive"))
      (node (ref "R25") (pin "2") (pinfunction "2_2") (pintype "passive"))
      (node (ref "U1") (pin "1") (pinfunction "VIN_1") (pintype "power_in"))
      (node (ref "U1") (pin "15") (pinfunction "VIN_15") (pintype "power_in"))
      (node (ref "U1") (pin "16") (pinfunction "VIN_16") (pintype "power_in"))
      (node (ref "U1") (pin "2") (pinfunction "VIN_2") (pintype "power_in"))
      (node (ref "U1") (pin "3") (pinfunction "VIN_3") (pintype "power_in"))
      (node (ref "U2") (pin "1") (pinfunction "VIN_1") (pintype "power_in"))
      (node (ref "U2") (pin "15") (pinfunction "VIN_15") (pintype "power_in"))
      (node (ref "U2") (pin "16") (pinfunction "VIN_16") (pintype "power_in"))
      (node (ref "U2") (pin "2") (pinfunction "VIN_2") (pintype "power_in"))
      (node (ref "U2") (pin "3") (pinfunction "VIN_3") (pintype "power_in"))
    )
    (net (code "22") (name "P3V3") (class "Default")
      (node (ref "C37") (pin "2") (pinfunction "2_2") (pintype "passive"))
      (node (ref "C38") (pin "2") (pinfunction "2_2") (pintype "passive"))
      (node (ref "L7") (pin "1") (pinfunction "1_1") (pintype "passive"))
    )
    (net (code "23") (name "P12V0") (class "Default")
      (node (ref "C50") (pin "2") (pinfunction "2_2") (pintype "passive"))
      (node (ref "C51") (pin "2") (pinfunction "2_2") (pintype "passive"))
      (node (ref "L10") (pin "1") (pinfunction "1_1") (pintype "passive"))
    )
    (net (code "24") (name "P12V0A") (class "Default")
      (node (ref "C52") (pin "1") (pinfunction "1_1") (pintype "passive"))
      (node (ref "C53") (pin "2") (pinfunction "2_2") (pintype "passive"))
      (node (ref "C54") (pin "2") (pinfunction "2_2") (pintype "passive"))
      (node (ref "C55") (pin "2") (pinfunction "2_2") (pintype "passive"))
      (node (ref "L10") (pin "2") (pinfunction "2_2") (pintype "passive"))
    )
    (net (code "25") (name "VADJ") (class "Default")
      (node (ref "C28") (pin "2") (pinfunction "2_2") (pintype "passive"))
      (node (ref "C29") (pin "2") (pinfunction "2_2") (pintype "passive"))
      (node (ref "L6") (pin "1") (pinfunction "1_1") (pintype "passive"))
    )
    (net (code "26") (name "VDDA_GPO") (class "Default")
      (node (ref "C2") (pin "2") (pinfunction "2_2") (pintype "passive"))
      (node (ref "C24") (pin "2") (pinfunction "2_2") (pintype "passive"))
      (node (ref "C25") (pin "2") (pinfunction "2_2") (pintype "passive"))
      (node (ref "C26") (pin "2") (pinfunction "2_2") (pintype "passive"))
      (node (ref "C27") (pin "2") (pinfunction "2_2") (pintype "passive"))
      (node (ref "L1") (pin "2") (pinfunction "2_2") (pintype "passive"))
    )
    (net (code "27") (name "VDD_INTERFACE") (class "Default")
      (node (ref "C30") (pin "2") (pinfunction "2_2") (pintype "passive"))
      (node (ref "C31") (pin "2") (pinfunction "2_2") (pintype "passive"))
      (node (ref "C32") (pin "2") (pinfunction "2_2") (pintype "passive"))
      (node (ref "C33") (pin "2") (pinfunction "2_2") (pintype "passive"))
      (node (ref "C34") (pin "2") (pinfunction "2_2") (pintype "passive"))
      (node (ref "C35") (pin "2") (pinfunction "2_2") (pintype "passive"))
      (node (ref "L6") (pin "2") (pinfunction "2_2") (pintype "passive"))
      (node (ref "R30") (pin "2") (pinfunction "2_2") (pintype "passive"))
      (node (ref "R34") (pin "2") (pinfunction "2_2") (pintype "passive"))
    )
    (net (code "28") (name "unconnected-(U1-NC-Pad8)") (class "Default")
      (node (ref "U1") (pin "8") (pinfunction "NC_8") (pintype "passive+no_connect"))
    )
    (net (code "29") (name "unconnected-(U2-NC-Pad8)") (class "Default")
      (node (ref "U2") (pin "8") (pinfunction "NC_8") (pintype "passive+no_connect"))
    )
  )
)
